# circuit.net
KiCad netlist of a schematic drawn in EasyEDA
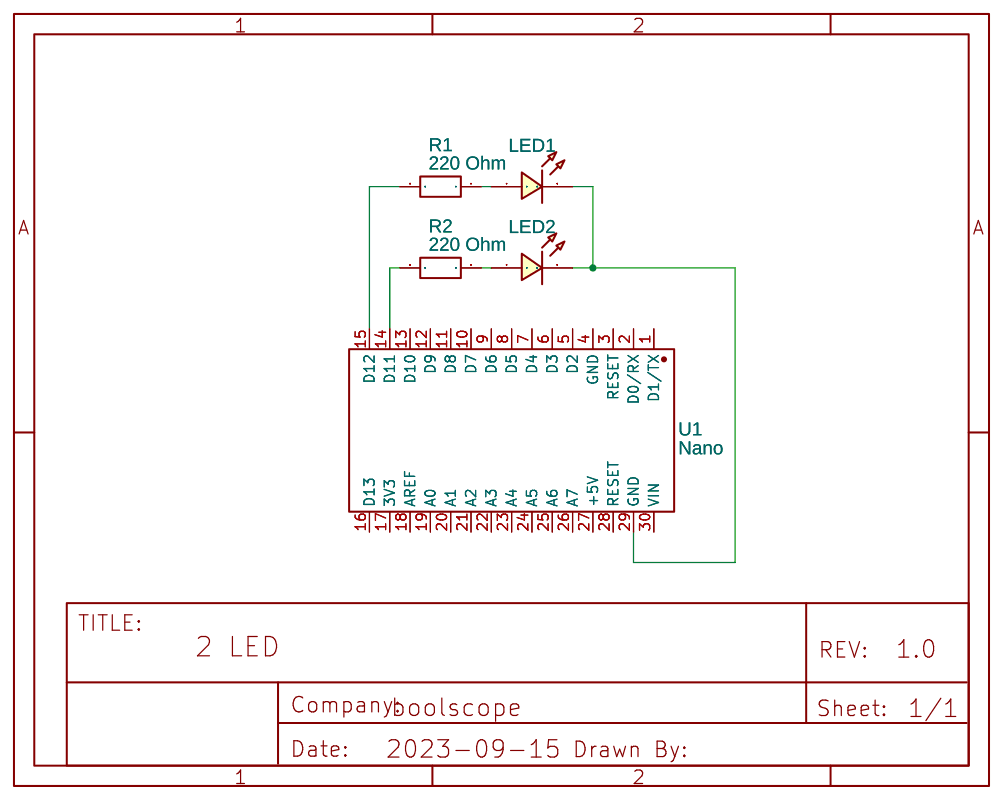
[diagram p0: schematic sheet]

(export (version "E")
  (design (tool "Eeschema 10.0.6"))
  (components
    (comp (ref "LED1")
      (value "LED-0603_R")
      (fields
        (field (name "Manufacturer Part") "19-217/R6C-AL1M2VY/3T")
        (field (name "Manufacturer") "EVERLIGHT(台湾亿光)")
      )
      (libsource (lib "") (part "LED-0603_R"))
    )
    (comp (ref "LED2")
      (value "LED-0603_R")
      (fields
        (field (name "Manufacturer Part") "19-217/R6C-AL1M2VY/3T")
        (field (name "Manufacturer") "EVERLIGHT(台湾亿光)")
      )
      (libsource (lib "") (part "LED-0603_R"))
    )
    (comp (ref "R1") (value "220 Ohm") (libsource (lib "") (part "R_0603_EU")))
    (comp (ref "R2") (value "220 Ohm") (libsource (lib "") (part "R_0603_EU")))
    (comp (ref "U1")
      (value "Nano")
      (fields (field (name "Manufacturer Part") "ARDUINO_NANO"))
      (libsource (lib "") (part "ARDUINO_NANO"))
    )
  )
  (nets
    (net (code "1") (name "Net-(LED1-Pad1)") (class "Default")
      (node (ref "LED1") (pin "1") (pinfunction "1_1") (pintype "unspecified"))
      (node (ref "R1") (pin "1") (pinfunction "1_1") (pintype "unspecified"))
    )
    (net (code "2") (name "Net-(LED1-Pad2)") (class "Default")
      (node (ref "LED1") (pin "2") (pinfunction "2_2") (pintype "unspecified"))
      (node (ref "LED2") (pin "2") (pinfunction "2_2") (pintype "unspecified"))
      (node (ref "U1") (pin "29") (pinfunction "GND_29") (pintype "unspecified"))
    )
    (net (code "3") (name "Net-(LED2-Pad1)") (class "Default")
      (node (ref "LED2") (pin "1") (pinfunction "1_1") (pintype "unspecified"))
      (node (ref "R2") (pin "1") (pinfunction "1_1") (pintype "unspecified"))
    )
    (net (code "4") (name "Net-(U1-D11)") (class "Default")
      (node (ref "R2") (pin "2") (pinfunction "2_2") (pintype "unspecified"))
      (node (ref "U1") (pin "14") (pinfunction "D11_14") (pintype "unspecified"))
    )
    (net (code "5") (name "Net-(U1-D12)") (class "Default")
      (node (ref "R1") (pin "2") (pinfunction "2_2") (pintype "unspecified"))
      (node (ref "U1") (pin "15") (pinfunction "D12_15") (pintype "unspecified"))
    )
    (net (code "6") (name "unconnected-(U1-+5V-Pad27)") (class "Default")
      (node (ref "U1") (pin "27") (pinfunction "+5V_27") (pintype "unspecified"))
    )
    (net (code "7") (name "unconnected-(U1-3V3-Pad17)") (class "Default")
      (node (ref "U1") (pin "17") (pinfunction "3V3_17") (pintype "unspecified"))
    )
    (net (code "8") (name "unconnected-(U1-A0-Pad19)") (class "Default")
      (node (ref "U1") (pin "19") (pinfunction "A0_19") (pintype "unspecified"))
    )
    (net (code "9") (name "unconnected-(U1-A1-Pad20)") (class "Default")
      (node (ref "U1") (pin "20") (pinfunction "A1_20") (pintype "unspecified"))
    )
    (net (code "10") (name "unconnected-(U1-A2-Pad21)") (class "Default")
      (node (ref "U1") (pin "21") (pinfunction "A2_21") (pintype "unspecified"))
    )
    (net (code "11") (name "unconnected-(U1-A3-Pad22)") (class "Default")
      (node (ref "U1") (pin "22") (pinfunction "A3_22") (pintype "unspecified"))
    )
    (net (code "12") (name "unconnected-(U1-A4-Pad23)") (class "Default")
      (node (ref "U1") (pin "23") (pinfunction "A4_23") (pintype "unspecified"))
    )
    (net (code "13") (name "unconnected-(U1-A5-Pad24)") (class "Default")
      (node (ref "U1") (pin "24") (pinfunction "A5_24") (pintype "unspecified"))
    )
    (net (code "14") (name "unconnected-(U1-A6-Pad25)") (class "Default")
      (node (ref "U1") (pin "25") (pinfunction "A6_25") (pintype "unspecified"))
    )
    (net (code "15") (name "unconnected-(U1-A7-Pad26)") (class "Default")
      (node (ref "U1") (pin "26") (pinfunction "A7_26") (pintype "unspecified"))
    )
    (net (code "16") (name "unconnected-(U1-AREF-Pad18)") (class "Default")
      (node (ref "U1") (pin "18") (pinfunction "AREF_18") (pintype "unspecified"))
    )
    (net (code "17") (name "unconnected-(U1-D0{slash}RX-Pad2)") (class "Default")
      (node (ref "U1") (pin "2") (pinfunction "D0/RX_2") (pintype "unspecified"))
    )
    (net (code "18") (name "unconnected-(U1-D1{slash}TX-Pad1)") (class "Default")
      (node (ref "U1") (pin "1") (pinfunction "D1/TX_1") (pintype "unspecified"))
    )
    (net (code "19") (name "unconnected-(U1-D2-Pad5)") (class "Default")
      (node (ref "U1") (pin "5") (pinfunction "D2_5") (pintype "unspecified"))
    )
    (net (code "20") (name "unconnected-(U1-D3-Pad6)") (class "Default")
      (node (ref "U1") (pin "6") (pinfunction "D3_6") (pintype "unspecified"))
    )
    (net (code "21") (name "unconnected-(U1-D4-Pad7)") (class "Default")
      (node (ref "U1") (pin "7") (pinfunction "D4_7") (pintype "unspecified"))
    )
    (net (code "22") (name "unconnected-(U1-D5-Pad8)") (class "Default")
      (node (ref "U1") (pin "8") (pinfunction "D5_8") (pintype "unspecified"))
    )
    (net (code "23") (name "unconnected-(U1-D6-Pad9)") (class "Default")
      (node (ref "U1") (pin "9") (pinfunction "D6_9") (pintype "unspecified"))
    )
    (net (code "24") (name "unconnected-(U1-D7-Pad10)") (class "Default")
      (node (ref "U1") (pin "10") (pinfunction "D7_10") (pintype "unspecified"))
    )
    (net (code "25") (name "unconnected-(U1-D8-Pad11)") (class "Default")
      (node (ref "U1") (pin "11") (pinfunction "D8_11") (pintype "unspecified"))
    )
    (net (code "26") (name "unconnected-(U1-D9-Pad12)") (class "Default")
      (node (ref "U1") (pin "12") (pinfunction "D9_12") (pintype "unspecified"))
    )
    (net (code "27") (name "unconnected-(U1-D10-Pad13)") (class "Default")
      (node (ref "U1") (pin "13") (pinfunction "D10_13") (pintype "unspecified"))
    )
    (net (code "28") (name "unconnected-(U1-D13-Pad16)") (class "Default")
      (node (ref "U1") (pin "16") (pinfunction "D13_16") (pintype "unspecified"))
    )
    (net (code "29") (name "unconnected-(U1-GND-Pad4)") (class "Default")
      (node (ref "U1") (pin "4") (pinfunction "GND_4") (pintype "unspecified"))
    )
    (net (code "30") (name "unconnected-(U1-RESET-Pad3)") (class "Default")
      (node (ref "U1") (pin "3") (pinfunction "RESET_3") (pintype "unspecified"))
    )
    (net (code "31") (name "unconnected-(U1-RESET-Pad28)") (class "Default")
      (node (ref "U1") (pin "28") (pinfunction "RESET_28") (pintype "unspecified"))
    )
    (net (code "32") (name "unconnected-(U1-VIN-Pad30)") (class "Default")
      (node (ref "U1") (pin "30") (pinfunction "VIN_30") (pintype "unspecified"))
    )
  )
)
